# SE-Exp30.net
KiCad netlist of a schematic drawn in EAGLE
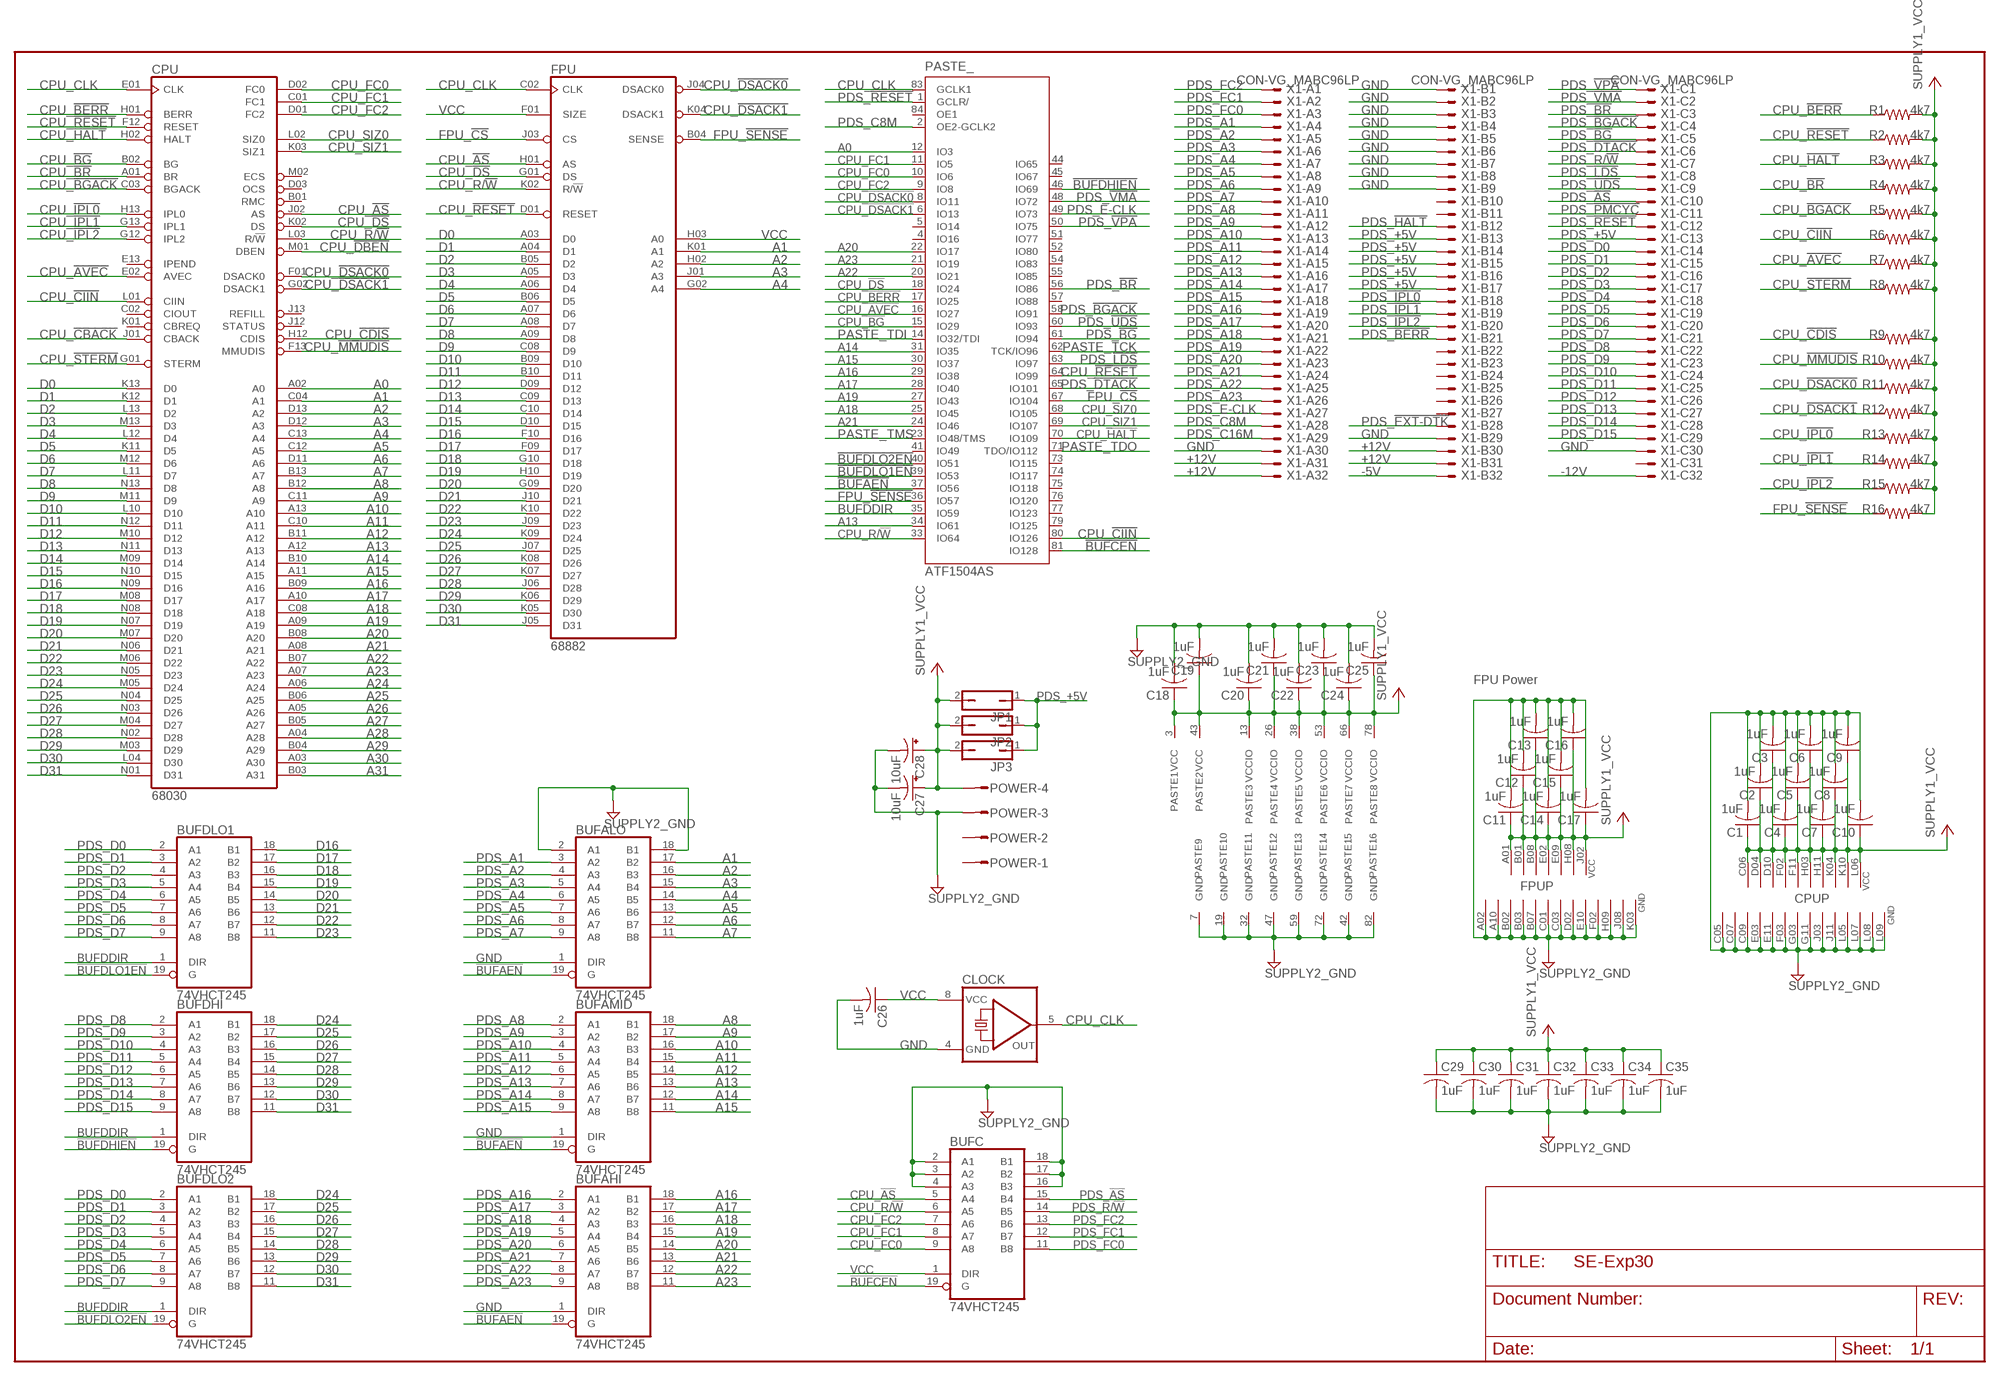
[diagram p0: schematic, sheet 1]

(export (version "E")
  (design (tool "Eeschema 10.0.6"))
  (components
    (comp (ref "BUFAHI")
      (value "74VHCT245")
      (footprint "eagle-import:74XX-US_SO20W")
      (libsource (lib "eagle-import") (part "74XX-US_74245DWLS"))
    )
    (comp (ref "BUFALO")
      (value "74VHCT245")
      (footprint "eagle-import:74XX-US_SO20W")
      (libsource (lib "eagle-import") (part "74XX-US_74245DWLS"))
    )
    (comp (ref "BUFAMID")
      (value "74VHCT245")
      (footprint "eagle-import:74XX-US_SO20W")
      (libsource (lib "eagle-import") (part "74XX-US_74245DWLS"))
    )
    (comp (ref "BUFC")
      (value "74VHCT245")
      (footprint "eagle-import:74XX-US_SO20W")
      (libsource (lib "eagle-import") (part "74XX-US_74245DWLS"))
    )
    (comp (ref "BUFDHI")
      (value "74VHCT245")
      (footprint "eagle-import:74XX-US_SO20W")
      (libsource (lib "eagle-import") (part "74XX-US_74245DWLS"))
    )
    (comp (ref "BUFDLO1")
      (value "74VHCT245")
      (footprint "eagle-import:74XX-US_SO20W")
      (libsource (lib "eagle-import") (part "74XX-US_74245DWLS"))
    )
    (comp (ref "BUFDLO2")
      (value "74VHCT245")
      (footprint "eagle-import:74XX-US_SO20W")
      (libsource (lib "eagle-import") (part "74XX-US_74245DWLS"))
    )
    (comp (ref "C1")
      (value "1uF")
      (footprint "eagle-import:RCL_C0805")
      (libsource (lib "eagle-import") (part "RCL_C-USC0805"))
    )
    (comp (ref "C2")
      (value "1uF")
      (footprint "eagle-import:RCL_C0805")
      (libsource (lib "eagle-import") (part "RCL_C-USC0805"))
    )
    (comp (ref "C3")
      (value "1uF")
      (footprint "eagle-import:RCL_C0805")
      (libsource (lib "eagle-import") (part "RCL_C-USC0805"))
    )
    (comp (ref "C4")
      (value "1uF")
      (footprint "eagle-import:RCL_C0805")
      (libsource (lib "eagle-import") (part "RCL_C-USC0805"))
    )
    (comp (ref "C5")
      (value "1uF")
      (footprint "eagle-import:RCL_C0805")
      (libsource (lib "eagle-import") (part "RCL_C-USC0805"))
    )
    (comp (ref "C6")
      (value "1uF")
      (footprint "eagle-import:RCL_C0805")
      (libsource (lib "eagle-import") (part "RCL_C-USC0805"))
    )
    (comp (ref "C7")
      (value "1uF")
      (footprint "eagle-import:RCL_C0805")
      (libsource (lib "eagle-import") (part "RCL_C-USC0805"))
    )
    (comp (ref "C8")
      (value "1uF")
      (footprint "eagle-import:RCL_C0805")
      (libsource (lib "eagle-import") (part "RCL_C-USC0805"))
    )
    (comp (ref "C9")
      (value "1uF")
      (footprint "eagle-import:RCL_C0805")
      (libsource (lib "eagle-import") (part "RCL_C-USC0805"))
    )
    (comp (ref "C10")
      (value "1uF")
      (footprint "eagle-import:RCL_C0805")
      (libsource (lib "eagle-import") (part "RCL_C-USC0805"))
    )
    (comp (ref "C11")
      (value "1uF")
      (footprint "eagle-import:RCL_C0805")
      (libsource (lib "eagle-import") (part "RCL_C-USC0805"))
    )
    (comp (ref "C12")
      (value "1uF")
      (footprint "eagle-import:RCL_C0805")
      (libsource (lib "eagle-import") (part "RCL_C-USC0805"))
    )
    (comp (ref "C13")
      (value "1uF")
      (footprint "eagle-import:RCL_C0805")
      (libsource (lib "eagle-import") (part "RCL_C-USC0805"))
    )
    (comp (ref "C14")
      (value "1uF")
      (footprint "eagle-import:RCL_C0805")
      (libsource (lib "eagle-import") (part "RCL_C-USC0805"))
    )
    (comp (ref "C15")
      (value "1uF")
      (footprint "eagle-import:RCL_C0805")
      (libsource (lib "eagle-import") (part "RCL_C-USC0805"))
    )
    (comp (ref "C16")
      (value "1uF")
      (footprint "eagle-import:RCL_C0805")
      (libsource (lib "eagle-import") (part "RCL_C-USC0805"))
    )
    (comp (ref "C17")
      (value "1uF")
      (footprint "eagle-import:RCL_C0805")
      (libsource (lib "eagle-import") (part "RCL_C-USC0805"))
    )
    (comp (ref "C18")
      (value "1uF")
      (footprint "eagle-import:RCL_C0805")
      (libsource (lib "eagle-import") (part "RCL_C-USC0805"))
    )
    (comp (ref "C19")
      (value "1uF")
      (footprint "eagle-import:RCL_C0805")
      (libsource (lib "eagle-import") (part "RCL_C-USC0805"))
    )
    (comp (ref "C20")
      (value "1uF")
      (footprint "eagle-import:RCL_C0805")
      (libsource (lib "eagle-import") (part "RCL_C-USC0805"))
    )
    (comp (ref "C21")
      (value "1uF")
      (footprint "eagle-import:RCL_C0805")
      (libsource (lib "eagle-import") (part "RCL_C-USC0805"))
    )
    (comp (ref "C22")
      (value "1uF")
      (footprint "eagle-import:RCL_C0805")
      (libsource (lib "eagle-import") (part "RCL_C-USC0805"))
    )
    (comp (ref "C23")
      (value "1uF")
      (footprint "eagle-import:RCL_C0805")
      (libsource (lib "eagle-import") (part "RCL_C-USC0805"))
    )
    (comp (ref "C24")
      (value "1uF")
      (footprint "eagle-import:RCL_C0805")
      (libsource (lib "eagle-import") (part "RCL_C-USC0805"))
    )
    (comp (ref "C25")
      (value "1uF")
      (footprint "eagle-import:RCL_C0805")
      (libsource (lib "eagle-import") (part "RCL_C-USC0805"))
    )
    (comp (ref "C26")
      (value "1uF")
      (footprint "eagle-import:RCL_C0805")
      (libsource (lib "eagle-import") (part "RCL_C-USC0805"))
    )
    (comp (ref "C27")
      (value "10uF")
      (footprint "eagle-import:RCL_E2,5-5")
      (libsource (lib "eagle-import") (part "RCL_CPOL-USE2.5-5"))
    )
    (comp (ref "C28")
      (value "10uF")
      (footprint "eagle-import:RCL_E2,5-5")
      (libsource (lib "eagle-import") (part "RCL_CPOL-USE2.5-5"))
    )
    (comp (ref "C29")
      (value "1uF")
      (footprint "eagle-import:RCL_C0805")
      (libsource (lib "eagle-import") (part "RCL_C-USC0805"))
    )
    (comp (ref "C30")
      (value "1uF")
      (footprint "eagle-import:RCL_C0805")
      (libsource (lib "eagle-import") (part "RCL_C-USC0805"))
    )
    (comp (ref "C31")
      (value "1uF")
      (footprint "eagle-import:RCL_C0805")
      (libsource (lib "eagle-import") (part "RCL_C-USC0805"))
    )
    (comp (ref "C32")
      (value "1uF")
      (footprint "eagle-import:RCL_C0805")
      (libsource (lib "eagle-import") (part "RCL_C-USC0805"))
    )
    (comp (ref "C33")
      (value "1uF")
      (footprint "eagle-import:RCL_C0805")
      (libsource (lib "eagle-import") (part "RCL_C-USC0805"))
    )
    (comp (ref "C34")
      (value "1uF")
      (footprint "eagle-import:RCL_C0805")
      (libsource (lib "eagle-import") (part "RCL_C-USC0805"))
    )
    (comp (ref "C35")
      (value "1uF")
      (footprint "eagle-import:RCL_C0805")
      (libsource (lib "eagle-import") (part "RCL_C-USC0805"))
    )
    (comp (ref "CLOCK")
      (value "CRYSTAL_QG5460")
      (footprint "eagle-import:CRYSTAL_DIL08S")
      (libsource (lib "eagle-import") (part "CRYSTAL_QG5460"))
    )
    (comp (ref "CPU")
      (value "68030")
      (footprint "eagle-import:MICRO-MC68000_MPGA128")
      (fields (field (name "MF") "MOTOROLA") (field (name "MPN") "MC68030RC50C"))
      (libsource (lib "eagle-import") (part "MICRO-MC68000_MC68030RC"))
    )
    (comp (ref "FPU")
      (value "68882")
      (footprint "eagle-import:MICRO-MC68000_MPGA68")
      (libsource (lib "eagle-import") (part "MICRO-MC68000_MC68881RC"))
    )
    (comp (ref "JP1")
      (value "JUMPER_JP1Q")
      (footprint "eagle-import:JUMPER_JP1")
      (libsource (lib "eagle-import") (part "JUMPER_JP1Q"))
    )
    (comp (ref "JP2")
      (value "JUMPER_JP1Q")
      (footprint "eagle-import:JUMPER_JP1")
      (libsource (lib "eagle-import") (part "JUMPER_JP1Q"))
    )
    (comp (ref "JP3")
      (value "JUMPER_JP1Q")
      (footprint "eagle-import:JUMPER_JP1")
      (libsource (lib "eagle-import") (part "JUMPER_JP1Q"))
    )
    (comp (ref "PASTE")
      (value "ATF1504AS")
      (footprint "eagle-import:SE-EXP30_S84")
      (libsource (lib "eagle-import") (part "SE-EXP30_EPM7128-J84S"))
    )
    (comp (ref "POWER")
      (value "CON-AMP-MT_L04P")
      (footprint "eagle-import:CON-AMP-MT_L04P")
      (libsource (lib "eagle-import") (part "CON-AMP-MT_L04P"))
    )
    (comp (ref "R1")
      (value "4k7")
      (footprint "eagle-import:RCL_R0805")
      (libsource (lib "eagle-import") (part "RCL_R-US_R0805"))
    )
    (comp (ref "R2")
      (value "4k7")
      (footprint "eagle-import:RCL_R0805")
      (libsource (lib "eagle-import") (part "RCL_R-US_R0805"))
    )
    (comp (ref "R3")
      (value "4k7")
      (footprint "eagle-import:RCL_R0805")
      (libsource (lib "eagle-import") (part "RCL_R-US_R0805"))
    )
    (comp (ref "R4")
      (value "4k7")
      (footprint "eagle-import:RCL_R0805")
      (libsource (lib "eagle-import") (part "RCL_R-US_R0805"))
    )
    (comp (ref "R5")
      (value "4k7")
      (footprint "eagle-import:RCL_R0805")
      (libsource (lib "eagle-import") (part "RCL_R-US_R0805"))
    )
    (comp (ref "R6")
      (value "4k7")
      (footprint "eagle-import:RCL_R0805")
      (libsource (lib "eagle-import") (part "RCL_R-US_R0805"))
    )
    (comp (ref "R7")
      (value "4k7")
      (footprint "eagle-import:RCL_R0805")
      (libsource (lib "eagle-import") (part "RCL_R-US_R0805"))
    )
    (comp (ref "R8")
      (value "4k7")
      (footprint "eagle-import:RCL_R0805")
      (libsource (lib "eagle-import") (part "RCL_R-US_R0805"))
    )
    (comp (ref "R9")
      (value "4k7")
      (footprint "eagle-import:RCL_R0805")
      (libsource (lib "eagle-import") (part "RCL_R-US_R0805"))
    )
    (comp (ref "R10")
      (value "4k7")
      (footprint "eagle-import:RCL_R0805")
      (libsource (lib "eagle-import") (part "RCL_R-US_R0805"))
    )
    (comp (ref "R11")
      (value "4k7")
      (footprint "eagle-import:RCL_R0805")
      (libsource (lib "eagle-import") (part "RCL_R-US_R0805"))
    )
    (comp (ref "R12")
      (value "4k7")
      (footprint "eagle-import:RCL_R0805")
      (libsource (lib "eagle-import") (part "RCL_R-US_R0805"))
    )
    (comp (ref "R13")
      (value "4k7")
      (footprint "eagle-import:RCL_R0805")
      (libsource (lib "eagle-import") (part "RCL_R-US_R0805"))
    )
    (comp (ref "R14")
      (value "4k7")
      (footprint "eagle-import:RCL_R0805")
      (libsource (lib "eagle-import") (part "RCL_R-US_R0805"))
    )
    (comp (ref "R15")
      (value "4k7")
      (footprint "eagle-import:RCL_R0805")
      (libsource (lib "eagle-import") (part "RCL_R-US_R0805"))
    )
    (comp (ref "R16")
      (value "4k7")
      (footprint "eagle-import:RCL_R0805")
      (libsource (lib "eagle-import") (part "RCL_R-US_R0805"))
    )
    (comp (ref "X1")
      (value "CON-VG_MABC96LP")
      (footprint "eagle-import:CON-VG_MABC96LP")
      (libsource (lib "eagle-import") (part "CON-VG_MABC96LP"))
    )
  )
  (nets
    (net (code "1") (name "/+12V") (class "Default")
      (node (ref "X1") (pin "A31") (pinfunction "S_A31") (pintype "passive"))
      (node (ref "X1") (pin "A32") (pinfunction "S_A32") (pintype "passive"))
      (node (ref "X1") (pin "B30") (pinfunction "S_B30") (pintype "passive"))
      (node (ref "X1") (pin "B31") (pinfunction "S_B31") (pintype "passive"))
    )
    (net (code "2") (name "/-5V") (class "Default")
      (node (ref "X1") (pin "B32") (pinfunction "S_B32") (pintype "passive"))
    )
    (net (code "3") (name "/-12V") (class "Default")
      (node (ref "X1") (pin "C32") (pinfunction "S_C32") (pintype "passive"))
    )
    (net (code "4") (name "/A0") (class "Default")
      (node (ref "CPU") (pin "A02") (pinfunction "A0_A02") (pintype "output"))
      (node (ref "PASTE") (pin "12") (pinfunction "IO3_12") (pintype "bidirectional"))
    )
    (net (code "5") (name "/A1") (class "Default")
      (node (ref "BUFALO") (pin "17") (pinfunction "B2_17") (pintype "bidirectional"))
      (node (ref "CPU") (pin "C04") (pinfunction "A1_C04") (pintype "output"))
      (node (ref "FPU") (pin "K01") (pinfunction "A1_K01") (pintype "input"))
    )
    (net (code "6") (name "/A2") (class "Default")
      (node (ref "BUFALO") (pin "16") (pinfunction "B3_16") (pintype "bidirectional"))
      (node (ref "CPU") (pin "D13") (pinfunction "A2_D13") (pintype "output"))
      (node (ref "FPU") (pin "H02") (pinfunction "A2_H02") (pintype "input"))
    )
    (net (code "7") (name "/A3") (class "Default")
      (node (ref "BUFALO") (pin "15") (pinfunction "B4_15") (pintype "bidirectional"))
      (node (ref "CPU") (pin "D12") (pinfunction "A3_D12") (pintype "output"))
      (node (ref "FPU") (pin "J01") (pinfunction "A3_J01") (pintype "input"))
    )
    (net (code "8") (name "/A4") (class "Default")
      (node (ref "BUFALO") (pin "14") (pinfunction "B5_14") (pintype "bidirectional"))
      (node (ref "CPU") (pin "C13") (pinfunction "A4_C13") (pintype "output"))
      (node (ref "FPU") (pin "G02") (pinfunction "A4_G02") (pintype "input"))
    )
    (net (code "9") (name "/A5") (class "Default")
      (node (ref "BUFALO") (pin "13") (pinfunction "B6_13") (pintype "bidirectional"))
      (node (ref "CPU") (pin "C12") (pinfunction "A5_C12") (pintype "output"))
    )
    (net (code "10") (name "/A6") (class "Default")
      (node (ref "BUFALO") (pin "12") (pinfunction "B7_12") (pintype "bidirectional"))
      (node (ref "CPU") (pin "D11") (pinfunction "A6_D11") (pintype "output"))
    )
    (net (code "11") (name "/A7") (class "Default")
      (node (ref "BUFALO") (pin "11") (pinfunction "B8_11") (pintype "bidirectional"))
      (node (ref "CPU") (pin "B13") (pinfunction "A7_B13") (pintype "output"))
    )
    (net (code "12") (name "/A8") (class "Default")
      (node (ref "BUFAMID") (pin "18") (pinfunction "B1_18") (pintype "bidirectional"))
      (node (ref "CPU") (pin "B12") (pinfunction "A8_B12") (pintype "output"))
    )
    (net (code "13") (name "/A9") (class "Default")
      (node (ref "BUFAMID") (pin "17") (pinfunction "B2_17") (pintype "bidirectional"))
      (node (ref "CPU") (pin "C11") (pinfunction "A9_C11") (pintype "output"))
    )
    (net (code "14") (name "/A10") (class "Default")
      (node (ref "BUFAMID") (pin "16") (pinfunction "B3_16") (pintype "bidirectional"))
      (node (ref "CPU") (pin "A13") (pinfunction "A10_A13") (pintype "output"))
    )
    (net (code "15") (name "/A11") (class "Default")
      (node (ref "BUFAMID") (pin "15") (pinfunction "B4_15") (pintype "bidirectional"))
      (node (ref "CPU") (pin "C10") (pinfunction "A11_C10") (pintype "output"))
    )
    (net (code "16") (name "/A12") (class "Default")
      (node (ref "BUFAMID") (pin "14") (pinfunction "B5_14") (pintype "bidirectional"))
      (node (ref "CPU") (pin "B11") (pinfunction "A12_B11") (pintype "output"))
    )
    (net (code "17") (name "/A13") (class "Default")
      (node (ref "BUFAMID") (pin "13") (pinfunction "B6_13") (pintype "bidirectional"))
      (node (ref "CPU") (pin "A12") (pinfunction "A13_A12") (pintype "output"))
      (node (ref "PASTE") (pin "34") (pinfunction "IO61_34") (pintype "bidirectional"))
    )
    (net (code "18") (name "/A14") (class "Default")
      (node (ref "BUFAMID") (pin "12") (pinfunction "B7_12") (pintype "bidirectional"))
      (node (ref "CPU") (pin "B10") (pinfunction "A14_B10") (pintype "output"))
      (node (ref "PASTE") (pin "31") (pinfunction "IO35_31") (pintype "bidirectional"))
    )
    (net (code "19") (name "/A15") (class "Default")
      (node (ref "BUFAMID") (pin "11") (pinfunction "B8_11") (pintype "bidirectional"))
      (node (ref "CPU") (pin "A11") (pinfunction "A15_A11") (pintype "output"))
      (node (ref "PASTE") (pin "30") (pinfunction "IO37_30") (pintype "bidirectional"))
    )
    (net (code "20") (name "/A16") (class "Default")
      (node (ref "BUFAHI") (pin "18") (pinfunction "B1_18") (pintype "bidirectional"))
      (node (ref "CPU") (pin "B09") (pinfunction "A16_B09") (pintype "output"))
      (node (ref "PASTE") (pin "29") (pinfunction "IO38_29") (pintype "bidirectional"))
    )
    (net (code "21") (name "/A17") (class "Default")
      (node (ref "BUFAHI") (pin "17") (pinfunction "B2_17") (pintype "bidirectional"))
      (node (ref "CPU") (pin "A10") (pinfunction "A17_A10") (pintype "output"))
      (node (ref "PASTE") (pin "28") (pinfunction "IO40_28") (pintype "bidirectional"))
    )
    (net (code "22") (name "/A18") (class "Default")
      (node (ref "BUFAHI") (pin "16") (pinfunction "B3_16") (pintype "bidirectional"))
      (node (ref "CPU") (pin "C08") (pinfunction "A18_C08") (pintype "output"))
      (node (ref "PASTE") (pin "25") (pinfunction "IO45_25") (pintype "bidirectional"))
    )
    (net (code "23") (name "/A19") (class "Default")
      (node (ref "BUFAHI") (pin "15") (pinfunction "B4_15") (pintype "bidirectional"))
      (node (ref "CPU") (pin "A09") (pinfunction "A19_A09") (pintype "output"))
      (node (ref "PASTE") (pin "27") (pinfunction "IO43_27") (pintype "bidirectional"))
    )
    (net (code "24") (name "/A20") (class "Default")
      (node (ref "BUFAHI") (pin "14") (pinfunction "B5_14") (pintype "bidirectional"))
      (node (ref "CPU") (pin "B08") (pinfunction "A20_B08") (pintype "output"))
      (node (ref "PASTE") (pin "22") (pinfunction "IO17_22") (pintype "bidirectional"))
    )
    (net (code "25") (name "/A21") (class "Default")
      (node (ref "BUFAHI") (pin "13") (pinfunction "B6_13") (pintype "bidirectional"))
      (node (ref "CPU") (pin "A08") (pinfunction "A21_A08") (pintype "output"))
      (node (ref "PASTE") (pin "24") (pinfunction "IO46_24") (pintype "bidirectional"))
    )
    (net (code "26") (name "/A22") (class "Default")
      (node (ref "BUFAHI") (pin "12") (pinfunction "B7_12") (pintype "bidirectional"))
      (node (ref "CPU") (pin "B07") (pinfunction "A22_B07") (pintype "output"))
      (node (ref "PASTE") (pin "20") (pinfunction "IO21_20") (pintype "bidirectional"))
    )
    (net (code "27") (name "/A23") (class "Default")
      (node (ref "BUFAHI") (pin "11") (pinfunction "B8_11") (pintype "bidirectional"))
      (node (ref "CPU") (pin "A07") (pinfunction "A23_A07") (pintype "output"))
      (node (ref "PASTE") (pin "21") (pinfunction "IO19_21") (pintype "bidirectional"))
    )
    (net (code "28") (name "/A24") (class "Default")
      (node (ref "CPU") (pin "A06") (pinfunction "A24_A06") (pintype "output"))
    )
    (net (code "29") (name "/A25") (class "Default")
      (node (ref "CPU") (pin "B06") (pinfunction "A25_B06") (pintype "output"))
    )
    (net (code "30") (name "/A26") (class "Default")
      (node (ref "CPU") (pin "A05") (pinfunction "A26_A05") (pintype "output"))
    )
    (net (code "31") (name "/A27") (class "Default")
      (node (ref "CPU") (pin "B05") (pinfunction "A27_B05") (pintype "output"))
    )
    (net (code "32") (name "/A28") (class "Default")
      (node (ref "CPU") (pin "A04") (pinfunction "A28_A04") (pintype "output"))
    )
    (net (code "33") (name "/A29") (class "Default")
      (node (ref "CPU") (pin "B04") (pinfunction "A29_B04") (pintype "output"))
    )
    (net (code "34") (name "/A30") (class "Default")
      (node (ref "CPU") (pin "A03") (pinfunction "A30_A03") (pintype "output"))
    )
    (net (code "35") (name "/A31") (class "Default")
      (node (ref "CPU") (pin "B03") (pinfunction "A31_B03") (pintype "output"))
    )
    (net (code "36") (name "/BUFDDIR") (class "Default")
      (node (ref "BUFDHI") (pin "1") (pinfunction "DIR_1") (pintype "input"))
      (node (ref "BUFDLO1") (pin "1") (pinfunction "DIR_1") (pintype "input"))
      (node (ref "BUFDLO2") (pin "1") (pinfunction "DIR_1") (pintype "input"))
      (node (ref "PASTE") (pin "35") (pinfunction "IO59_35") (pintype "bidirectional"))
    )
    (net (code "37") (name "/CPU_CLK") (class "Default")
      (node (ref "CLOCK") (pin "5") (pinfunction "OUT_5") (pintype "output"))
      (node (ref "CPU") (pin "E01") (pinfunction "CLK_E01") (pintype "input"))
      (node (ref "FPU") (pin "C02") (pinfunction "CLK_C02") (pintype "input"))
      (node (ref "PASTE") (pin "83") (pinfunction "GCLK1_83") (pintype "input"))
    )
    (net (code "38") (name "/CPU_FC0") (class "Default")
      (node (ref "BUFC") (pin "9") (pinfunction "A8_9") (pintype "bidirectional"))
      (node (ref "CPU") (pin "D02") (pinfunction "FC0_D02") (pintype "output"))
      (node (ref "PASTE") (pin "10") (pinfunction "IO6_10") (pintype "bidirectional"))
    )
    (net (code "39") (name "/CPU_FC1") (class "Default")
      (node (ref "BUFC") (pin "8") (pinfunction "A7_8") (pintype "bidirectional"))
      (node (ref "CPU") (pin "C01") (pinfunction "FC1_C01") (pintype "output"))
      (node (ref "PASTE") (pin "11") (pinfunction "IO5_11") (pintype "bidirectional"))
    )
    (net (code "40") (name "/CPU_FC2") (class "Default")
      (node (ref "BUFC") (pin "7") (pinfunction "A6_7") (pintype "bidirectional"))
      (node (ref "CPU") (pin "D01") (pinfunction "FC2_D01") (pintype "output"))
      (node (ref "PASTE") (pin "9") (pinfunction "IO8_9") (pintype "bidirectional"))
    )
    (net (code "41") (name "/CPU_R{slash}~{W}") (class "Default")
      (node (ref "BUFC") (pin "6") (pinfunction "A5_6") (pintype "bidirectional"))
      (node (ref "CPU") (pin "L03") (pinfunction "R/~{W}_L03") (pintype "output"))
      (node (ref "FPU") (pin "K02") (pinfunction "R/~{W}_K02") (pintype "input"))
      (node (ref "PASTE") (pin "33") (pinfunction "IO64_33") (pintype "bidirectional"))
    )
    (net (code "42") (name "/CPU_SIZ0") (class "Default")
      (node (ref "CPU") (pin "L02") (pinfunction "SIZ0_L02") (pintype "output"))
      (node (ref "PASTE") (pin "68") (pinfunction "IO105_68") (pintype "bidirectional"))
    )
    (net (code "43") (name "/CPU_SIZ1") (class "Default")
      (node (ref "CPU") (pin "K03") (pinfunction "SIZ1_K03") (pintype "output"))
      (node (ref "PASTE") (pin "69") (pinfunction "IO107_69") (pintype "bidirectional"))
    )
    (net (code "44") (name "/CPU_~{AS}") (class "Default")
      (node (ref "BUFC") (pin "5") (pinfunction "A4_5") (pintype "bidirectional"))
      (node (ref "CPU") (pin "J02") (pinfunction "AS_J02") (pintype "output"))
      (node (ref "FPU") (pin "H01") (pinfunction "AS_H01") (pintype "input"))
    )
    (net (code "45") (name "/CPU_~{AVEC}") (class "Default")
      (node (ref "CPU") (pin "E02") (pinfunction "AVEC_E02") (pintype "input"))
      (node (ref "PASTE") (pin "16") (pinfunction "IO27_16") (pintype "bidirectional"))
      (node (ref "R7") (pin "1") (pinfunction "1_1") (pintype "passive"))
    )
    (net (code "46") (name "/CPU_~{BERR}") (class "Default")
      (node (ref "CPU") (pin "H01") (pinfunction "BERR_H01") (pintype "input"))
      (node (ref "PASTE") (pin "17") (pinfunction "IO25_17") (pintype "bidirectional"))
      (node (ref "R1") (pin "1") (pinfunction "1_1") (pintype "passive"))
    )
    (net (code "47") (name "/CPU_~{BGACK}") (class "Default")
      (node (ref "CPU") (pin "C03") (pinfunction "BGACK_C03") (pintype "input"))
      (node (ref "R5") (pin "1") (pinfunction "1_1") (pintype "passive"))
    )
    (net (code "48") (name "/CPU_~{BG}") (class "Default")
      (node (ref "CPU") (pin "B02") (pinfunction "BG_B02") (pintype "output"))
      (node (ref "PASTE") (pin "15") (pinfunction "IO29_15") (pintype "bidirectional"))
    )
    (net (code "49") (name "/CPU_~{BR}") (class "Default")
      (node (ref "CPU") (pin "A01") (pinfunction "BR_A01") (pintype "input"))
      (node (ref "R4") (pin "1") (pinfunction "1_1") (pintype "passive"))
    )
    (net (code "50") (name "/CPU_~{CBACK}") (class "Default")
      (node (ref "CPU") (pin "J01") (pinfunction "CBACK_J01") (pintype "input"))
    )
    (net (code "51") (name "/CPU_~{CDIS}") (class "Default")
      (node (ref "CPU") (pin "H12") (pinfunction "CDIS_H12") (pintype "input"))
      (node (ref "R9") (pin "1") (pinfunction "1_1") (pintype "passive"))
    )
    (net (code "52") (name "/CPU_~{CIIN}") (class "Default")
      (node (ref "CPU") (pin "L01") (pinfunction "CIIN_L01") (pintype "input"))
      (node (ref "PASTE") (pin "80") (pinfunction "IO126_80") (pintype "bidirectional"))
      (node (ref "R6") (pin "1") (pinfunction "1_1") (pintype "passive"))
    )
    (net (code "53") (name "/CPU_~{DBEN}") (class "Default")
      (node (ref "CPU") (pin "M01") (pinfunction "DBEN_M01") (pintype "output"))
    )
    (net (code "54") (name "/CPU_~{DSACK0}") (class "Default")
      (node (ref "CPU") (pin "F01") (pinfunction "DSACK0_F01") (pintype "input"))
      (node (ref "FPU") (pin "J04") (pinfunction "DSACK0_J04") (pintype "output"))
      (node (ref "PASTE") (pin "8") (pinfunction "IO11_8") (pintype "bidirectional"))
      (node (ref "R11") (pin "1") (pinfunction "1_1") (pintype "passive"))
    )
    (net (code "55") (name "/CPU_~{DSACK1}") (class "Default")
      (node (ref "CPU") (pin "G02") (pinfunction "DSACK1_G02") (pintype "input"))
      (node (ref "FPU") (pin "K04") (pinfunction "DSACK1_K04") (pintype "output"))
      (node (ref "PASTE") (pin "6") (pinfunction "IO13_6") (pintype "bidirectional"))
      (node (ref "R12") (pin "1") (pinfunction "1_1") (pintype "passive"))
    )
    (net (code "56") (name "/CPU_~{DS}") (class "Default")
      (node (ref "CPU") (pin "K02") (pinfunction "DS_K02") (pintype "output"))
      (node (ref "FPU") (pin "G01") (pinfunction "DS_G01") (pintype "input"))
      (node (ref "PASTE") (pin "18") (pinfunction "IO24_18") (pintype "bidirectional"))
    )
    (net (code "57") (name "/CPU_~{HALT}") (class "Default")
      (node (ref "CPU") (pin "H02") (pinfunction "HALT_H02") (pintype "input"))
      (node (ref "PASTE") (pin "70") (pinfunction "IO109_70") (pintype "bidirectional"))
      (node (ref "R3") (pin "1") (pinfunction "1_1") (pintype "passive"))
    )
    (net (code "58") (name "/CPU_~{IPL0}") (class "Default")
      (node (ref "CPU") (pin "H13") (pinfunction "IPL0_H13") (pintype "input"))
      (node (ref "R13") (pin "1") (pinfunction "1_1") (pintype "passive"))
    )
    (net (code "59") (name "/CPU_~{IPL1}") (class "Default")
      (node (ref "CPU") (pin "G13") (pinfunction "IPL1_G13") (pintype "input"))
      (node (ref "R14") (pin "1") (pinfunction "1_1") (pintype "passive"))
    )
    (net (code "60") (name "/CPU_~{IPL2}") (class "Default")
      (node (ref "CPU") (pin "G12") (pinfunction "IPL2_G12") (pintype "input"))
      (node (ref "R15") (pin "1") (pinfunction "1_1") (pintype "passive"))
    )
    (net (code "61") (name "/CPU_~{MMUDIS}") (class "Default")
      (node (ref "CPU") (pin "F13") (pinfunction "MMUDIS_F13") (pintype "input"))
      (node (ref "R10") (pin "1") (pinfunction "1_1") (pintype "passive"))
    )
    (net (code "62") (name "/CPU_~{RESET}") (class "Default")
      (node (ref "CPU") (pin "F12") (pinfunction "RESET_F12") (pintype "bidirectional"))
      (node (ref "FPU") (pin "D01") (pinfunction "RESET_D01") (pintype "input"))
      (node (ref "PASTE") (pin "64") (pinfunction "IO99_64") (pintype "bidirectional"))
      (node (ref "R2") (pin "1") (pinfunction "1_1") (pintype "passive"))
    )
    (net (code "63") (name "/CPU_~{STERM}") (class "Default")
      (node (ref "CPU") (pin "G01") (pinfunction "STERM_G01") (pintype "input"))
      (node (ref "R8") (pin "1") (pinfunction "1_1") (pintype "passive"))
    )
    (net (code "64") (name "/D0") (class "Default")
      (node (ref "CPU") (pin "K13") (pinfunction "D0_K13") (pintype "bidirectional"))
      (node (ref "FPU") (pin "A03") (pinfunction "D0_A03") (pintype "bidirectional"))
    )
    (net (code "65") (name "/D1") (class "Default")
      (node (ref "CPU") (pin "K12") (pinfunction "D1_K12") (pintype "bidirectional"))
      (node (ref "FPU") (pin "A04") (pinfunction "D1_A04") (pintype "bidirectional"))
    )
    (net (code "66") (name "/D2") (class "Default")
      (node (ref "CPU") (pin "L13") (pinfunction "D2_L13") (pintype "bidirectional"))
      (node (ref "FPU") (pin "B05") (pinfunction "D2_B05") (pintype "bidirectional"))
    )
    (net (code "67") (name "/D3") (class "Default")
      (node (ref "CPU") (pin "M13") (pinfunction "D3_M13") (pintype "bidirectional"))
      (node (ref "FPU") (pin "A05") (pinfunction "D3_A05") (pintype "bidirectional"))
    )
    (net (code "68") (name "/D4") (class "Default")
      (node (ref "CPU") (pin "L12") (pinfunction "D4_L12") (pintype "bidirectional"))
      (node (ref "FPU") (pin "A06") (pinfunction "D4_A06") (pintype "bidirectional"))
    )
    (net (code "69") (name "/D5") (class "Default")
      (node (ref "CPU") (pin "K11") (pinfunction "D5_K11") (pintype "bidirectional"))
      (node (ref "FPU") (pin "B06") (pinfunction "D5_B06") (pintype "bidirectional"))
    )
    (net (code "70") (name "/D6") (class "Default")
      (node (ref "CPU") (pin "M12") (pinfunction "D6_M12") (pintype "bidirectional"))
      (node (ref "FPU") (pin "A07") (pinfunction "D6_A07") (pintype "bidirectional"))
    )
    (net (code "71") (name "/D7") (class "Default")
      (node (ref "CPU") (pin "L11") (pinfunction "D7_L11") (pintype "bidirectional"))
      (node (ref "FPU") (pin "A08") (pinfunction "D7_A08") (pintype "bidirectional"))
    )
    (net (code "72") (name "/D8") (class "Default")
      (node (ref "CPU") (pin "N13") (pinfunction "D8_N13") (pintype "bidirectional"))
      (node (ref "FPU") (pin "A09") (pinfunction "D8_A09") (pintype "bidirectional"))
    )
    (net (code "73") (name "/D9") (class "Default")
      (node (ref "CPU") (pin "M11") (pinfunction "D9_M11") (pintype "bidirectional"))
      (node (ref "FPU") (pin "C08") (pinfunction "D9_C08") (pintype "bidirectional"))
    )
    (net (code "74") (name "/D10") (class "Default")
      (node (ref "CPU") (pin "L10") (pinfunction "D10_L10") (pintype "bidirectional"))
      (node (ref "FPU") (pin "B09") (pinfunction "D10_B09") (pintype "bidirectional"))
    )
    (net (code "75") (name "/D11") (class "Default")
      (node (ref "CPU") (pin "N12") (pinfunction "D11_N12") (pintype "bidirectional"))
      (node (ref "FPU") (pin "B10") (pinfunction "D11_B10") (pintype "bidirectional"))
    )
    (net (code "76") (name "/D12") (class "Default")
      (node (ref "CPU") (pin "M10") (pinfunction "D12_M10") (pintype "bidirectional"))
      (node (ref "FPU") (pin "D09") (pinfunction "D12_D09") (pintype "bidirectional"))
    )
    (net (code "77") (name "/D13") (class "Default")
      (node (ref "CPU") (pin "N11") (pinfunction "D13_N11") (pintype "bidirectional"))
      (node (ref "FPU") (pin "C09") (pinfunction "D13_C09") (pintype "bidirectional"))
    )
    (net (code "78") (name "/D14") (class "Default")
      (node (ref "CPU") (pin "M09") (pinfunction "D14_M09") (pintype "bidirectional"))
      (node (ref "FPU") (pin "C10") (pinfunction "D14_C10") (pintype "bidirectional"))
    )
    (net (code "79") (name "/D15") (class "Default")
      (node (ref "CPU") (pin "N10") (pinfunction "D15_N10") (pintype "bidirectional"))
      (node (ref "FPU") (pin "D10") (pinfunction "D15_D10") (pintype "bidirectional"))
    )
    (net (code "80") (name "/D16") (class "Default")
      (node (ref "BUFDLO1") (pin "18") (pinfunction "B1_18") (pintype "bidirectional"))
      (node (ref "CPU") (pin "N09") (pinfunction "D16_N09") (pintype "bidirectional"))
      (node (ref "FPU") (pin "F10") (pinfunction "D16_F10") (pintype "bidirectional"))
    )
    (net (code "81") (name "/D17") (class "Default")
      (node (ref "BUFDLO1") (pin "17") (pinfunction "B2_17") (pintype "bidirectional"))
      (node (ref "CPU") (pin "M08") (pinfunction "D17_M08") (pintype "bidirectional"))
      (node (ref "FPU") (pin "F09") (pinfunction "D17_F09") (pintype "bidirectional"))
    )
    (net (code "82") (name "/D18") (class "Default")
      (node (ref "BUFDLO1") (pin "16") (pinfunction "B3_16") (pintype "bidirectional"))
      (node (ref "CPU") (pin "N08") (pinfunction "D18_N08") (pintype "bidirectional"))
      (node (ref "FPU") (pin "G10") (pinfunction "D18_G10") (pintype "bidirectional"))
    )
    (net (code "83") (name "/D19") (class "Default")
      (node (ref "BUFDLO1") (pin "15") (pinfunction "B4_15") (pintype "bidirectional"))
      (node (ref "CPU") (pin "N07") (pinfunction "D19_N07") (pintype "bidirectional"))
      (node (ref "FPU") (pin "H10") (pinfunction "D19_H10") (pintype "bidirectional"))
    )
    (net (code "84") (name "/D20") (class "Default")
      (node (ref "BUFDLO1") (pin "14") (pinfunction "B5_14") (pintype "bidirectional"))
      (node (ref "CPU") (pin "M07") (pinfunction "D20_M07") (pintype "bidirectional"))
      (node (ref "FPU") (pin "G09") (pinfunction "D20_G09") (pintype "bidirectional"))
    )
    (net (code "85") (name "/D21") (class "Default")
      (node (ref "BUFDLO1") (pin "13") (pinfunction "B6_13") (pintype "bidirectional"))
      (node (ref "CPU") (pin "N06") (pinfunction "D21_N06") (pintype "bidirectional"))
      (node (ref "FPU") (pin "J10") (pinfunction "D21_J10") (pintype "bidirectional"))
    )
    (net (code "86") (name "/D22") (class "Default")
      (node (ref "BUFDLO1") (pin "12") (pinfunction "B7_12") (pintype "bidirectional"))
      (node (ref "CPU") (pin "M06") (pinfunction "D22_M06") (pintype "bidirectional"))
      (node (ref "FPU") (pin "K10") (pinfunction "D22_K10") (pintype "bidirectional"))
    )
    (net (code "87") (name "/D23") (class "Default")
      (node (ref "BUFDLO1") (pin "11") (pinfunction "B8_11") (pintype "bidirectional"))
      (node (ref "CPU") (pin "N05") (pinfunction "D23_N05") (pintype "bidirectional"))
      (node (ref "FPU") (pin "J09") (pinfunction "D23_J09") (pintype "bidirectional"))
    )
    (net (code "88") (name "/D24") (class "Default")
      (node (ref "BUFDHI") (pin "18") (pinfunction "B1_18") (pintype "bidirectional"))
      (node (ref "BUFDLO2") (pin "18") (pinfunction "B1_18") (pintype "bidirectional"))
      (node (ref "CPU") (pin "M05") (pinfunction "D24_M05") (pintype "bidirectional"))
      (node (ref "FPU") (pin "K09") (pinfunction "D24_K09") (pintype "bidirectional"))
    )
    (net (code "89") (name "/D25") (class "Default")
      (node (ref "BUFDHI") (pin "17") (pinfunction "B2_17") (pintype "bidirectional"))
      (node (ref "BUFDLO2") (pin "17") (pinfunction "B2_17") (pintype "bidirectional"))
      (node (ref "CPU") (pin "N04") (pinfunction "D25_N04") (pintype "bidirectional"))
      (node (ref "FPU") (pin "J07") (pinfunction "D25_J07") (pintype "bidirectional"))
    )
    (net (code "90") (name "/D26") (class "Default")
      (node (ref "BUFDHI") (pin "16") (pinfunction "B3_16") (pintype "bidirectional"))
      (node (ref "BUFDLO2") (pin "16") (pinfunction "B3_16") (pintype "bidirectional"))
      (node (ref "CPU") (pin "N03") (pinfunction "D26_N03") (pintype "bidirectional"))
      (node (ref "FPU") (pin "K08") (pinfunction "D26_K08") (pintype "bidirectional"))
    )
    (net (code "91") (name "/D27") (class "Default")
      (node (ref "BUFDHI") (pin "15") (pinfunction "B4_15") (pintype "bidirectional"))
      (node (ref "BUFDLO2") (pin "15") (pinfunction "B4_15") (pintype "bidirectional"))
      (node (ref "CPU") (pin "M04") (pinfunction "D27_M04") (pintype "bidirectional"))
      (node (ref "FPU") (pin "K07") (pinfunction "D27_K07") (pintype "bidirectional"))
    )
    (net (code "92") (name "/D28") (class "Default")
      (node (ref "BUFDHI") (pin "14") (pinfunction "B5_14") (pintype "bidirectional"))
      (node (ref "BUFDLO2") (pin "14") (pinfunction "B5_14") (pintype "bidirectional"))
      (node (ref "CPU") (pin "N02") (pinfunction "D28_N02") (pintype "bidirectional"))
      (node (ref "FPU") (pin "J06") (pinfunction "D28_J06") (pintype "bidirectional"))
    )
    (net (code "93") (name "/D29") (class "Default")
      (node (ref "BUFDHI") (pin "13") (pinfunction "B6_13") (pintype "bidirectional"))
      (node (ref "BUFDLO2") (pin "13") (pinfunction "B6_13") (pintype "bidirectional"))
      (node (ref "CPU") (pin "M03") (pinfunction "D29_M03") (pintype "bidirectional"))
      (node (ref "FPU") (pin "K06") (pinfunction "D29_K06") (pintype "bidirectional"))
    )
    (net (code "94") (name "/D30") (class "Default")
      (node (ref "BUFDHI") (pin "12") (pinfunction "B7_12") (pintype "bidirectional"))
      (node (ref "BUFDLO2") (pin "12") (pinfunction "B7_12") (pintype "bidirectional"))
      (node (ref "CPU") (pin "L04") (pinfunction "D30_L04") (pintype "bidirectional"))
      (node (ref "FPU") (pin "K05") (pinfunction "D30_K05") (pintype "bidirectional"))
    )
    (net (code "95") (name "/D31") (class "Default")
      (node (ref "BUFDHI") (pin "11") (pinfunction "B8_11") (pintype "bidirectional"))
      (node (ref "BUFDLO2") (pin "11") (pinfunction "B8_11") (pintype "bidirectional"))
      (node (ref "CPU") (pin "N01") (pinfunction "D31_N01") (pintype "bidirectional"))
      (node (ref "FPU") (pin "J05") (pinfunction "D31_J05") (pintype "bidirectional"))
    )
    (net (code "96") (name "/FPU_~{CS}") (class "Default")
      (node (ref "FPU") (pin "J03") (pinfunction "CS_J03") (pintype "input"))
      (node (ref "PASTE") (pin "67") (pinfunction "IO104_67") (pintype "bidirectional"))
    )
    (net (code "97") (name "/FPU_~{SENSE}") (class "Default")
      (node (ref "FPU") (pin "B04") (pinfunction "SENSE_B04") (pintype "bidirectional"))
      (node (ref "PASTE") (pin "36") (pinfunction "IO57_36") (pintype "bidirectional"))
      (node (ref "R16") (pin "1") (pinfunction "1_1") (pintype "passive"))
    )
    (net (code "98") (name "/PASTE_TCK") (class "Default")
      (node (ref "PASTE") (pin "62") (pinfunction "TCK/IO96_62") (pintype "bidirectional"))
    )
    (net (code "99") (name "/PASTE_TDI") (class "Default")
      (node (ref "PASTE") (pin "14") (pinfunction "IO32/TDI_14") (pintype "bidirectional"))
    )
    (net (code "100") (name "/PASTE_TDO") (class "Default")
      (node (ref "PASTE") (pin "71") (pinfunction "TDO/IO112_71") (pintype "bidirectional"))
    )
    (net (code "101") (name "/PASTE_TMS") (class "Default")
      (node (ref "PASTE") (pin "23") (pinfunction "IO48/TMS_23") (pintype "bidirectional"))
    )
    (net (code "102") (name "/PDS_+5V") (class "Default")
      (node (ref "JP1") (pin "1") (pinfunction "1_1") (pintype "passive"))
      (node (ref "JP2") (pin "1") (pinfunction "1_1") (pintype "passive"))
      (node (ref "JP3") (pin "1") (pinfunction "1_1") (pintype "passive"))
      (node (ref "X1") (pin "B13") (pinfunction "S_B13") (pintype "passive"))
      (node (ref "X1") (pin "B14") (pinfunction "S_B14") (pintype "passive"))
      (node (ref "X1") (pin "B15") (pinfunction "S_B15") (pintype "passive"))
      (node (ref "X1") (pin "B16") (pinfunction "S_B16") (pintype "passive"))
      (node (ref "X1") (pin "B17") (pinfunction "S_B17") (pintype "passive"))
      (node (ref "X1") (pin "C13") (pinfunction "S_C13") (pintype "passive"))
    )
    (net (code "103") (name "/PDS_A1") (class "Default")
      (node (ref "BUFALO") (pin "3") (pinfunction "A2_3") (pintype "bidirectional"))
      (node (ref "X1") (pin "A4") (pinfunction "S_A4") (pintype "passive"))
    )
    (net (code "104") (name "/PDS_A2") (class "Default")
      (node (ref "BUFALO") (pin "4") (pinfunction "A3_4") (pintype "bidirectional"))
      (node (ref "X1") (pin "A5") (pinfunction "S_A5") (pintype "passive"))
    )
    (net (code "105") (name "/PDS_A3") (class "Default")
      (node (ref "BUFALO") (pin "5") (pinfunction "A4_5") (pintype "bidirectional"))
      (node (ref "X1") (pin "A6") (pinfunction "S_A6") (pintype "passive"))
    )
    (net (code "106") (name "/PDS_A4") (class "Default")
      (node (ref "BUFALO") (pin "6") (pinfunction "A5_6") (pintype "bidirectional"))
      (node (ref "X1") (pin "A7") (pinfunction "S_A7") (pintype "passive"))
    )
    (net (code "107") (name "/PDS_A5") (class "Default")
      (node (ref "BUFALO") (pin "7") (pinfunction "A6_7") (pintype "bidirectional"))
      (node (ref "X1") (pin "A8") (pinfunction "S_A8") (pintype "passive"))
    )
    (net (code "108") (name "/PDS_A6") (class "Default")
      (node (ref "BUFALO") (pin "8") (pinfunction "A7_8") (pintype "bidirectional"))
      (node (ref "X1") (pin "A9") (pinfunction "S_A9") (pintype "passive"))
    )
    (net (code "109") (name "/PDS_A7") (class "Default")
      (node (ref "BUFALO") (pin "9") (pinfunction "A8_9") (pintype "bidirectional"))
      (node (ref "X1") (pin "A10") (pinfunction "S_A10") (pintype "passive"))
    )
    (net (code "110") (name "/PDS_A8") (class "Default")
      (node (ref "BUFAMID") (pin "2") (pinfunction "A1_2") (pintype "bidirectional"))
      (node (ref "X1") (pin "A11") (pinfunction "S_A11") (pintype "passive"))
    )
    (net (code "111") (name "/PDS_A9") (class "Default")
      (node (ref "BUFAMID") (pin "3") (pinfunction "A2_3") (pintype "bidirectional"))
      (node (ref "X1") (pin "A12") (pinfunction "S_A12") (pintype "passive"))
    )
    (net (code "112") (name "/PDS_A10") (class "Default")
      (node (ref "BUFAMID") (pin "4") (pinfunction "A3_4") (pintype "bidirectional"))
      (node (ref "X1") (pin "A13") (pinfunction "S_A13") (pintype "passive"))
    )
    (net (code "113") (name "/PDS_A11") (class "Default")
      (node (ref "BUFAMID") (pin "5") (pinfunction "A4_5") (pintype "bidirectional"))
      (node (ref "X1") (pin "A14") (pinfunction "S_A14") (pintype "passive"))
    )
    (net (code "114") (name "/PDS_A12") (class "Default")
      (node (ref "BUFAMID") (pin "6") (pinfunction "A5_6") (pintype "bidirectional"))
      (node (ref "X1") (pin "A15") (pinfunction "S_A15") (pintype "passive"))
    )
    (net (code "115") (name "/PDS_A13") (class "Default")
      (node (ref "BUFAMID") (pin "7") (pinfunction "A6_7") (pintype "bidirectional"))
      (node (ref "X1") (pin "A16") (pinfunction "S_A16") (pintype "passive"))
    )
    (net (code "116") (name "/PDS_A14") (class "Default")
      (node (ref "BUFAMID") (pin "8") (pinfunction "A7_8") (pintype "bidirectional"))
      (node (ref "X1") (pin "A17") (pinfunction "S_A17") (pintype "passive"))
    )
    (net (code "117") (name "/PDS_A15") (class "Default")
      (node (ref "BUFAMID") (pin "9") (pinfunction "A8_9") (pintype "bidirectional"))
      (node (ref "X1") (pin "A18") (pinfunction "S_A18") (pintype "passive"))
    )
    (net (code "118") (name "/PDS_A16") (class "Default")
      (node (ref "BUFAHI") (pin "2") (pinfunction "A1_2") (pintype "bidirectional"))
      (node (ref "X1") (pin "A19") (pinfunction "S_A19") (pintype "passive"))
    )
    (net (code "119") (name "/PDS_A17") (class "Default")
      (node (ref "BUFAHI") (pin "3") (pinfunction "A2_3") (pintype "bidirectional"))
      (node (ref "X1") (pin "A20") (pinfunction "S_A20") (pintype "passive"))
    )
    (net (code "120") (name "/PDS_A18") (class "Default")
      (node (ref "BUFAHI") (pin "4") (pinfunction "A3_4") (pintype "bidirectional"))
      (node (ref "X1") (pin "A21") (pinfunction "S_A21") (pintype "passive"))
    )
    (net (code "121") (name "/PDS_A19") (class "Default")
      (node (ref "BUFAHI") (pin "5") (pinfunction "A4_5") (pintype "bidirectional"))
      (node (ref "X1") (pin "A22") (pinfunction "S_A22") (pintype "passive"))
    )
    (net (code "122") (name "/PDS_A20") (class "Default")
      (node (ref "BUFAHI") (pin "6") (pinfunction "A5_6") (pintype "bidirectional"))
      (node (ref "X1") (pin "A23") (pinfunction "S_A23") (pintype "passive"))
    )
    (net (code "123") (name "/PDS_A21") (class "Default")
      (node (ref "BUFAHI") (pin "7") (pinfunction "A6_7") (pintype "bidirectional"))
      (node (ref "X1") (pin "A24") (pinfunction "S_A24") (pintype "passive"))
    )
    (net (code "124") (name "/PDS_A22") (class "Default")
      (node (ref "BUFAHI") (pin "8") (pinfunction "A7_8") (pintype "bidirectional"))
      (node (ref "X1") (pin "A25") (pinfunction "S_A25") (pintype "passive"))
    )
    (net (code "125") (name "/PDS_A23") (class "Default")
      (node (ref "BUFAHI") (pin "9") (pinfunction "A8_9") (pintype "bidirectional"))
      (node (ref "X1") (pin "A26") (pinfunction "S_A26") (pintype "passive"))
    )
    (net (code "126") (name "/PDS_C8M") (class "Default")
      (node (ref "PASTE") (pin "2") (pinfunction "OE2-GCLK2_2") (pintype "input"))
      (node (ref "X1") (pin "A28") (pinfunction "S_A28") (pintype "passive"))
    )
    (net (code "127") (name "/PDS_C16M") (class "Default")
      (node (ref "X1") (pin "A29") (pinfunction "S_A29") (pintype "passive"))
    )
    (net (code "128") (name "/PDS_D0") (class "Default")
      (node (ref "BUFDLO1") (pin "2") (pinfunction "A1_2") (pintype "bidirectional"))
      (node (ref "BUFDLO2") (pin "2") (pinfunction "A1_2") (pintype "bidirectional"))
      (node (ref "X1") (pin "C14") (pinfunction "S_C14") (pintype "passive"))
    )
    (net (code "129") (name "/PDS_D1") (class "Default")
      (node (ref "BUFDLO1") (pin "3") (pinfunction "A2_3") (pintype "bidirectional"))
      (node (ref "BUFDLO2") (pin "3") (pinfunction "A2_3") (pintype "bidirectional"))
      (node (ref "X1") (pin "C15") (pinfunction "S_C15") (pintype "passive"))
    )
    (net (code "130") (name "/PDS_D2") (class "Default")
      (node (ref "BUFDLO1") (pin "4") (pinfunction "A3_4") (pintype "bidirectional"))
      (node (ref "BUFDLO2") (pin "4") (pinfunction "A3_4") (pintype "bidirectional"))
      (node (ref "X1") (pin "C16") (pinfunction "S_C16") (pintype "passive"))
    )
    (net (code "131") (name "/PDS_D3") (class "Default")
      (node (ref "BUFDLO1") (pin "5") (pinfunction "A4_5") (pintype "bidirectional"))
      (node (ref "BUFDLO2") (pin "5") (pinfunction "A4_5") (pintype "bidirectional"))
      (node (ref "X1") (pin "C17") (pinfunction "S_C17") (pintype "passive"))
    )
    (net (code "132") (name "/PDS_D4") (class "Default")
      (node (ref "BUFDLO1") (pin "6") (pinfunction "A5_6") (pintype "bidirectional"))
      (node (ref "BUFDLO2") (pin "6") (pinfunction "A5_6") (pintype "bidirectional"))
      (node (ref "X1") (pin "C18") (pinfunction "S_C18") (pintype "passive"))
    )
    (net (code "133") (name "/PDS_D5") (class "Default")
      (node (ref "BUFDLO1") (pin "7") (pinfunction "A6_7") (pintype "bidirectional"))
      (node (ref "BUFDLO2") (pin "7") (pinfunction "A6_7") (pintype "bidirectional"))
      (node (ref "X1") (pin "C19") (pinfunction "S_C19") (pintype "passive"))
    )
    (net (code "134") (name "/PDS_D6") (class "Default")
      (node (ref "BUFDLO1") (pin "8") (pinfunction "A7_8") (pintype "bidirectional"))
      (node (ref "BUFDLO2") (pin "8") (pinfunction "A7_8") (pintype "bidirectional"))
      (node (ref "X1") (pin "C20") (pinfunction "S_C20") (pintype "passive"))
    )
    (net (code "135") (name "/PDS_D7") (class "Default")
      (node (ref "BUFDLO1") (pin "9") (pinfunction "A8_9") (pintype "bidirectional"))
      (node (ref "BUFDLO2") (pin "9") (pinfunction "A8_9") (pintype "bidirectional"))
      (node (ref "X1") (pin "C21") (pinfunction "S_C21") (pintype "passive"))
    )
    (net (code "136") (name "/PDS_D8") (class "Default")
      (node (ref "BUFDHI") (pin "2") (pinfunction "A1_2") (pintype "bidirectional"))
      (node (ref "X1") (pin "C22") (pinfunction "S_C22") (pintype "passive"))
    )
    (net (code "137") (name "/PDS_D9") (class "Default")
      (node (ref "BUFDHI") (pin "3") (pinfunction "A2_3") (pintype "bidirectional"))
      (node (ref "X1") (pin "C23") (pinfunction "S_C23") (pintype "passive"))
    )
    (net (code "138") (name "/PDS_D10") (class "Default")
      (node (ref "BUFDHI") (pin "4") (pinfunction "A3_4") (pintype "bidirectional"))
      (node (ref "X1") (pin "C24") (pinfunction "S_C24") (pintype "passive"))
    )
    (net (code "139") (name "/PDS_D11") (class "Default")
      (node (ref "BUFDHI") (pin "5") (pinfunction "A4_5") (pintype "bidirectional"))
      (node (ref "X1") (pin "C25") (pinfunction "S_C25") (pintype "passive"))
    )
    (net (code "140") (name "/PDS_D12") (class "Default")
      (node (ref "BUFDHI") (pin "6") (pinfunction "A5_6") (pintype "bidirectional"))
      (node (ref "X1") (pin "C26") (pinfunction "S_C26") (pintype "passive"))
    )
    (net (code "141") (name "/PDS_D13") (class "Default")
      (node (ref "BUFDHI") (pin "7") (pinfunction "A6_7") (pintype "bidirectional"))
      (node (ref "X1") (pin "C27") (pinfunction "S_C27") (pintype "passive"))
    )
    (net (code "142") (name "/PDS_D14") (class "Default")
      (node (ref "BUFDHI") (pin "8") (pinfunction "A7_8") (pintype "bidirectional"))
      (node (ref "X1") (pin "C28") (pinfunction "S_C28") (pintype "passive"))
    )
    (net (code "143") (name "/PDS_D15") (class "Default")
      (node (ref "BUFDHI") (pin "9") (pinfunction "A8_9") (pintype "bidirectional"))
      (node (ref "X1") (pin "C29") (pinfunction "S_C29") (pintype "passive"))
    )
    (net (code "144") (name "/PDS_E-CLK") (class "Default")
      (node (ref "PASTE") (pin "49") (pinfunction "IO73_49") (pintype "bidirectional"))
      (node (ref "X1") (pin "A27") (pinfunction "S_A27") (pintype "passive"))
    )
    (net (code "145") (name "/PDS_FC0") (class "Default")
      (node (ref "BUFC") (pin "11") (pinfunction "B8_11") (pintype "bidirectional"))
      (node (ref "X1") (pin "A3") (pinfunction "S_A3") (pintype "passive"))
    )
    (net (code "146") (name "/PDS_FC1") (class "Default")
      (node (ref "BUFC") (pin "12") (pinfunction "B7_12") (pintype "bidirectional"))
      (node (ref "X1") (pin "A2") (pinfunction "S_A2") (pintype "passive"))
    )
    (net (code "147") (name "/PDS_FC2") (class "Default")
      (node (ref "BUFC") (pin "13") (pinfunction "B6_13") (pintype "bidirectional"))
      (node (ref "X1") (pin "A1") (pinfunction "S_A1") (pintype "passive"))
    )
    (net (code "148") (name "/PDS_R{slash}~{W}") (class "Default")
      (node (ref "BUFC") (pin "14") (pinfunction "B5_14") (pintype "bidirectional"))
      (node (ref "X1") (pin "C7") (pinfunction "S_C7") (pintype "passive"))
    )
    (net (code "149") (name "/PDS_~{AS}") (class "Default")
      (node (ref "BUFC") (pin "15") (pinfunction "B4_15") (pintype "bidirectional"))
      (node (ref "X1") (pin "C10") (pinfunction "S_C10") (pintype "passive"))
    )
    (net (code "150") (name "/PDS_~{BERR}") (class "Default")
      (node (ref "X1") (pin "B21") (pinfunction "S_B21") (pintype "passive"))
    )
    (net (code "151") (name "/PDS_~{BGACK}") (class "Default")
      (node (ref "PASTE") (pin "58") (pinfunction "IO91_58") (pintype "bidirectional"))
      (node (ref "X1") (pin "C4") (pinfunction "S_C4") (pintype "passive"))
    )
    (net (code "152") (name "/PDS_~{BG}") (class "Default")
      (node (ref "PASTE") (pin "61") (pinfunction "IO94_61") (pintype "bidirectional"))
      (node (ref "X1") (pin "C5") (pinfunction "S_C5") (pintype "passive"))
    )
    (net (code "153") (name "/PDS_~{BR}") (class "Default")
      (node (ref "PASTE") (pin "56") (pinfunction "IO86_56") (pintype "bidirectional"))
      (node (ref "X1") (pin "C3") (pinfunction "S_C3") (pintype "passive"))
    )
    (net (code "154") (name "/PDS_~{DTACK}") (class "Default")
      (node (ref "PASTE") (pin "65") (pinfunction "IO101_65") (pintype "bidirectional"))
      (node (ref "X1") (pin "C6") (pinfunction "S_C6") (pintype "passive"))
    )
    (net (code "155") (name "/PDS_~{EXT-DTK}") (class "Default")
      (node (ref "X1") (pin "B28") (pinfunction "S_B28") (pintype "passive"))
    )
    (net (code "156") (name "/PDS_~{HALT}") (class "Default")
      (node (ref "X1") (pin "B12") (pinfunction "S_B12") (pintype "passive"))
    )
    (net (code "157") (name "/PDS_~{IPL0}") (class "Default")
      (node (ref "X1") (pin "B18") (pinfunction "S_B18") (pintype "passive"))
    )
    (net (code "158") (name "/PDS_~{IPL1}") (class "Default")
      (node (ref "X1") (pin "B19") (pinfunction "S_B19") (pintype "passive"))
    )
    (net (code "159") (name "/PDS_~{IPL2}") (class "Default")
      (node (ref "X1") (pin "B20") (pinfunction "S_B20") (pintype "passive"))
    )
    (net (code "160") (name "/PDS_~{LDS}") (class "Default")
      (node (ref "PASTE") (pin "63") (pinfunction "IO97_63") (pintype "bidirectional"))
      (node (ref "X1") (pin "C8") (pinfunction "S_C8") (pintype "passive"))
    )
    (net (code "161") (name "/PDS_~{PMCYC}") (class "Default")
      (node (ref "X1") (pin "C11") (pinfunction "S_C11") (pintype "passive"))
    )
    (net (code "162") (name "/PDS_~{RESET}") (class "Default")
      (node (ref "PASTE") (pin "1") (pinfunction "GCLR/_1") (pintype "input"))
      (node (ref "X1") (pin "C12") (pinfunction "S_C12") (pintype "passive"))
    )
    (net (code "163") (name "/PDS_~{UDS}") (class "Default")
      (node (ref "PASTE") (pin "60") (pinfunction "IO93_60") (pintype "bidirectional"))
      (node (ref "X1") (pin "C9") (pinfunction "S_C9") (pintype "passive"))
    )
    (net (code "164") (name "/PDS_~{VMA}") (class "Default")
      (node (ref "PASTE") (pin "48") (pinfunction "IO72_48") (pintype "bidirectional"))
      (node (ref "X1") (pin "C2") (pinfunction "S_C2") (pintype "passive"))
    )
    (net (code "165") (name "/PDS_~{VPA}") (class "Default")
      (node (ref "PASTE") (pin "50") (pinfunction "IO75_50") (pintype "bidirectional"))
      (node (ref "X1") (pin "C1") (pinfunction "S_C1") (pintype "passive"))
    )
    (net (code "166") (name "/~{BUFAEN}") (class "Default")
      (node (ref "BUFAHI") (pin "19") (pinfunction "G_19") (pintype "input"))
      (node (ref "BUFALO") (pin "19") (pinfunction "G_19") (pintype "input"))
      (node (ref "BUFAMID") (pin "19") (pinfunction "G_19") (pintype "input"))
      (node (ref "PASTE") (pin "37") (pinfunction "IO56_37") (pintype "bidirectional"))
    )
    (net (code "167") (name "/~{BUFCEN}") (class "Default")
      (node (ref "BUFC") (pin "19") (pinfunction "G_19") (pintype "input"))
      (node (ref "PASTE") (pin "81") (pinfunction "IO128_81") (pintype "bidirectional"))
    )
    (net (code "168") (name "/~{BUFDHIEN}") (class "Default")
      (node (ref "BUFDHI") (pin "19") (pinfunction "G_19") (pintype "input"))
      (node (ref "PASTE") (pin "46") (pinfunction "IO69_46") (pintype "bidirectional"))
    )
    (net (code "169") (name "/~{BUFDLO1EN}") (class "Default")
      (node (ref "BUFDLO1") (pin "19") (pinfunction "G_19") (pintype "input"))
      (node (ref "PASTE") (pin "39") (pinfunction "IO53_39") (pintype "bidirectional"))
    )
    (net (code "170") (name "/~{BUFDLO2EN}") (class "Default")
      (node (ref "BUFDLO2") (pin "19") (pinfunction "G_19") (pintype "input"))
      (node (ref "PASTE") (pin "40") (pinfunction "IO51_40") (pintype "bidirectional"))
    )
    (net (code "171") (name "SUPPLY1_VCC") (class "Default")
      (node (ref "BUFC") (pin "1") (pinfunction "DIR_1") (pintype "input"))
      (node (ref "C1") (pin "1") (pinfunction "1_1") (pintype "passive"))
      (node (ref "C10") (pin "1") (pinfunction "1_1") (pintype "passive"))
      (node (ref "C11") (pin "1") (pinfunction "1_1") (pintype "passive"))
      (node (ref "C12") (pin "1") (pinfunction "1_1") (pintype "passive"))
      (node (ref "C13") (pin "1") (pinfunction "1_1") (pintype "passive"))
      (node (ref "C14") (pin "1") (pinfunction "1_1") (pintype "passive"))
      (node (ref "C15") (pin "1") (pinfunction "1_1") (pintype "passive"))
      (node (ref "C16") (pin "1") (pinfunction "1_1") (pintype "passive"))
      (node (ref "C17") (pin "1") (pinfunction "1_1") (pintype "passive"))
      (node (ref "C18") (pin "1") (pinfunction "1_1") (pintype "passive"))
      (node (ref "C19") (pin "1") (pinfunction "1_1") (pintype "passive"))
      (node (ref "C2") (pin "1") (pinfunction "1_1") (pintype "passive"))
      (node (ref "C20") (pin "1") (pinfunction "1_1") (pintype "passive"))
      (node (ref "C21") (pin "1") (pinfunction "1_1") (pintype "passive"))
      (node (ref "C22") (pin "1") (pinfunction "1_1") (pintype "passive"))
      (node (ref "C23") (pin "1") (pinfunction "1_1") (pintype "passive"))
      (node (ref "C24") (pin "1") (pinfunction "1_1") (pintype "passive"))
      (node (ref "C25") (pin "1") (pinfunction "1_1") (pintype "passive"))
      (node (ref "C26") (pin "1") (pinfunction "1_1") (pintype "passive"))
      (node (ref "C27") (pin "+") (pinfunction "+_+") (pintype "passive"))
      (node (ref "C28") (pin "+") (pinfunction "+_+") (pintype "passive"))
      (node (ref "C29") (pin "1") (pinfunction "1_1") (pintype "passive"))
      (node (ref "C3") (pin "1") (pinfunction "1_1") (pintype "passive"))
      (node (ref "C30") (pin "1") (pinfunction "1_1") (pintype "passive"))
      (node (ref "C31") (pin "1") (pinfunction "1_1") (pintype "passive"))
      (node (ref "C32") (pin "1") (pinfunction "1_1") (pintype "passive"))
      (node (ref "C33") (pin "1") (pinfunction "1_1") (pintype "passive"))
      (node (ref "C34") (pin "1") (pinfunction "1_1") (pintype "passive"))
      (node (ref "C35") (pin "1") (pinfunction "1_1") (pintype "passive"))
      (node (ref "C4") (pin "1") (pinfunction "1_1") (pintype "passive"))
      (node (ref "C5") (pin "1") (pinfunction "1_1") (pintype "passive"))
      (node (ref "C6") (pin "1") (pinfunction "1_1") (pintype "passive"))
      (node (ref "C7") (pin "1") (pinfunction "1_1") (pintype "passive"))
      (node (ref "C8") (pin "1") (pinfunction "1_1") (pintype "passive"))
      (node (ref "C9") (pin "1") (pinfunction "1_1") (pintype "passive"))
      (node (ref "CLOCK") (pin "8") (pinfunction "VCC_8") (pintype "power_in"))
      (node (ref "CPU") (pin "C06") (pinfunction "VCC_C06") (pintype "power_in"))
      (node (ref "CPU") (pin "D04") (pinfunction "VCC_D04") (pintype "power_in"))
      (node (ref "CPU") (pin "D10") (pinfunction "VCC_D10") (pintype "power_in"))
      (node (ref "CPU") (pin "F02") (pinfunction "VCC_F02") (pintype "power_in"))
      (node (ref "CPU") (pin "F11") (pinfunction "VCC_F11") (pintype "power_in"))
      (node (ref "CPU") (pin "H03") (pinfunction "VCC_H03") (pintype "power_in"))
      (node (ref "CPU") (pin "H11") (pinfunction "VCC_H11") (pintype "power_in"))
      (node (ref "CPU") (pin "K04") (pinfunction "VCC_K04") (pintype "power_in"))
      (node (ref "CPU") (pin "K10") (pinfunction "VCC_K10") (pintype "power_in"))
      (node (ref "CPU") (pin "L06") (pinfunction "VCC_L06") (pintype "power_in"))
      (node (ref "FPU") (pin "A01") (pinfunction "VCC_A01") (pintype "power_in"))
      (node (ref "FPU") (pin "B01") (pinfunction "VCC_B01") (pintype "power_in"))
      (node (ref "FPU") (pin "B08") (pinfunction "VCC_B08") (pintype "power_in"))
      (node (ref "FPU") (pin "E02") (pinfunction "VCC_E02") (pintype "power_in"))
      (node (ref "FPU") (pin "E09") (pinfunction "VCC_E09") (pintype "power_in"))
      (node (ref "FPU") (pin "F01") (pinfunction "SIZE_F01") (pintype "input"))
      (node (ref "FPU") (pin "H03") (pinfunction "A0_H03") (pintype "input"))
      (node (ref "FPU") (pin "H08") (pinfunction "VCC_H08") (pintype "power_in"))
      (node (ref "FPU") (pin "J02") (pinfunction "VCC_J02") (pintype "power_in"))
      (node (ref "JP1") (pin "2") (pinfunction "2_2") (pintype "passive"))
      (node (ref "JP2") (pin "2") (pinfunction "2_2") (pintype "passive"))
      (node (ref "JP3") (pin "2") (pinfunction "2_2") (pintype "passive"))
      (node (ref "PASTE") (pin "13") (pinfunction "VCCIO_13") (pintype "power_in"))
      (node (ref "PASTE") (pin "26") (pinfunction "VCCIO_26") (pintype "power_in"))
      (node (ref "PASTE") (pin "3") (pinfunction "VCC_3") (pintype "power_in"))
      (node (ref "PASTE") (pin "38") (pinfunction "VCCIO_38") (pintype "power_in"))
      (node (ref "PASTE") (pin "43") (pinfunction "VCC_43") (pintype "power_in"))
      (node (ref "PASTE") (pin "53") (pinfunction "VCCIO_53") (pintype "power_in"))
      (node (ref "PASTE") (pin "66") (pinfunction "VCCIO_66") (pintype "power_in"))
      (node (ref "PASTE") (pin "78") (pinfunction "VCCIO_78") (pintype "power_in"))
      (node (ref "POWER") (pin "4") (pinfunction "S_4") (pintype "passive"))
      (node (ref "R1") (pin "2") (pinfunction "2_2") (pintype "passive"))
      (node (ref "R10") (pin "2") (pinfunction "2_2") (pintype "passive"))
      (node (ref "R11") (pin "2") (pinfunction "2_2") (pintype "passive"))
      (node (ref "R12") (pin "2") (pinfunction "2_2") (pintype "passive"))
      (node (ref "R13") (pin "2") (pinfunction "2_2") (pintype "passive"))
      (node (ref "R14") (pin "2") (pinfunction "2_2") (pintype "passive"))
      (node (ref "R15") (pin "2") (pinfunction "2_2") (pintype "passive"))
      (node (ref "R16") (pin "2") (pinfunction "2_2") (pintype "passive"))
      (node (ref "R2") (pin "2") (pinfunction "2_2") (pintype "passive"))
      (node (ref "R3") (pin "2") (pinfunction "2_2") (pintype "passive"))
      (node (ref "R4") (pin "2") (pinfunction "2_2") (pintype "passive"))
      (node (ref "R5") (pin "2") (pinfunction "2_2") (pintype "passive"))
      (node (ref "R6") (pin "2") (pinfunction "2_2") (pintype "passive"))
      (node (ref "R7") (pin "2") (pinfunction "2_2") (pintype "passive"))
      (node (ref "R8") (pin "2") (pinfunction "2_2") (pintype "passive"))
      (node (ref "R9") (pin "2") (pinfunction "2_2") (pintype "passive"))
    )
    (net (code "172") (name "SUPPLY2_GND") (class "Default")
      (node (ref "BUFAHI") (pin "1") (pinfunction "DIR_1") (pintype "input"))
      (node (ref "BUFALO") (pin "1") (pinfunction "DIR_1") (pintype "input"))
      (node (ref "BUFALO") (pin "18") (pinfunction "B1_18") (pintype "bidirectional"))
      (node (ref "BUFALO") (pin "2") (pinfunction "A1_2") (pintype "bidirectional"))
      (node (ref "BUFAMID") (pin "1") (pinfunction "DIR_1") (pintype "input"))
      (node (ref "BUFC") (pin "16") (pinfunction "B3_16") (pintype "bidirectional"))
      (node (ref "BUFC") (pin "17") (pinfunction "B2_17") (pintype "bidirectional"))
      (node (ref "BUFC") (pin "18") (pinfunction "B1_18") (pintype "bidirectional"))
      (node (ref "BUFC") (pin "2") (pinfunction "A1_2") (pintype "bidirectional"))
      (node (ref "BUFC") (pin "3") (pinfunction "A2_3") (pintype "bidirectional"))
      (node (ref "BUFC") (pin "4") (pinfunction "A3_4") (pintype "bidirectional"))
      (node (ref "C1") (pin "2") (pinfunction "2_2") (pintype "passive"))
      (node (ref "C10") (pin "2") (pinfunction "2_2") (pintype "passive"))
      (node (ref "C11") (pin "2") (pinfunction "2_2") (pintype "passive"))
      (node (ref "C12") (pin "2") (pinfunction "2_2") (pintype "passive"))
      (node (ref "C13") (pin "2") (pinfunction "2_2") (pintype "passive"))
      (node (ref "C14") (pin "2") (pinfunction "2_2") (pintype "passive"))
      (node (ref "C15") (pin "2") (pinfunction "2_2") (pintype "passive"))
      (node (ref "C16") (pin "2") (pinfunction "2_2") (pintype "passive"))
      (node (ref "C17") (pin "2") (pinfunction "2_2") (pintype "passive"))
      (node (ref "C18") (pin "2") (pinfunction "2_2") (pintype "passive"))
      (node (ref "C19") (pin "2") (pinfunction "2_2") (pintype "passive"))
      (node (ref "C2") (pin "2") (pinfunction "2_2") (pintype "passive"))
      (node (ref "C20") (pin "2") (pinfunction "2_2") (pintype "passive"))
      (node (ref "C21") (pin "2") (pinfunction "2_2") (pintype "passive"))
      (node (ref "C22") (pin "2") (pinfunction "2_2") (pintype "passive"))
      (node (ref "C23") (pin "2") (pinfunction "2_2") (pintype "passive"))
      (node (ref "C24") (pin "2") (pinfunction "2_2") (pintype "passive"))
      (node (ref "C25") (pin "2") (pinfunction "2_2") (pintype "passive"))
      (node (ref "C26") (pin "2") (pinfunction "2_2") (pintype "passive"))
      (node (ref "C27") (pin "-") (pinfunction "-_-") (pintype "passive"))
      (node (ref "C28") (pin "-") (pinfunction "-_-") (pintype "passive"))
      (node (ref "C29") (pin "2") (pinfunction "2_2") (pintype "passive"))
      (node (ref "C3") (pin "2") (pinfunction "2_2") (pintype "passive"))
      (node (ref "C30") (pin "2") (pinfunction "2_2") (pintype "passive"))
      (node (ref "C31") (pin "2") (pinfunction "2_2") (pintype "passive"))
      (node (ref "C32") (pin "2") (pinfunction "2_2") (pintype "passive"))
      (node (ref "C33") (pin "2") (pinfunction "2_2") (pintype "passive"))
      (node (ref "C34") (pin "2") (pinfunction "2_2") (pintype "passive"))
      (node (ref "C35") (pin "2") (pinfunction "2_2") (pintype "passive"))
      (node (ref "C4") (pin "2") (pinfunction "2_2") (pintype "passive"))
      (node (ref "C5") (pin "2") (pinfunction "2_2") (pintype "passive"))
      (node (ref "C6") (pin "2") (pinfunction "2_2") (pintype "passive"))
      (node (ref "C7") (pin "2") (pinfunction "2_2") (pintype "passive"))
      (node (ref "C8") (pin "2") (pinfunction "2_2") (pintype "passive"))
      (node (ref "C9") (pin "2") (pinfunction "2_2") (pintype "passive"))
      (node (ref "CLOCK") (pin "4") (pinfunction "GND_4") (pintype "power_in"))
      (node (ref "CPU") (pin "C05") (pinfunction "GND_C05") (pintype "power_in"))
      (node (ref "CPU") (pin "C07") (pinfunction "GND_C07") (pintype "power_in"))
      (node (ref "CPU") (pin "C09") (pinfunction "GND_C09") (pintype "power_in"))
      (node (ref "CPU") (pin "E03") (pinfunction "GND_E03") (pintype "power_in"))
      (node (ref "CPU") (pin "E11") (pinfunction "GND_E11") (pintype "power_in"))
      (node (ref "CPU") (pin "F03") (pinfunction "GND_F03") (pintype "power_in"))
      (node (ref "CPU") (pin "G03") (pinfunction "GND_G03") (pintype "power_in"))
      (node (ref "CPU") (pin "G11") (pinfunction "GND_G11") (pintype "power_in"))
      (node (ref "CPU") (pin "J03") (pinfunction "GND_J03") (pintype "power_in"))
      (node (ref "CPU") (pin "J11") (pinfunction "GND_J11") (pintype "power_in"))
      (node (ref "CPU") (pin "L05") (pinfunction "GND_L05") (pintype "power_in"))
      (node (ref "CPU") (pin "L07") (pinfunction "GND_L07") (pintype "power_in"))
      (node (ref "CPU") (pin "L08") (pinfunction "GND_L08") (pintype "power_in"))
      (node (ref "CPU") (pin "L09") (pinfunction "GND_L09") (pintype "power_in"))
      (node (ref "FPU") (pin "A02") (pinfunction "GND_A02") (pintype "power_in"))
      (node (ref "FPU") (pin "A10") (pinfunction "GND_A10") (pintype "power_in"))
      (node (ref "FPU") (pin "B02") (pinfunction "GND_B02") (pintype "power_in"))
      (node (ref "FPU") (pin "B03") (pinfunction "GND_B03") (pintype "power_in"))
      (node (ref "FPU") (pin "B07") (pinfunction "GND_B07") (pintype "power_in"))
      (node (ref "FPU") (pin "C01") (pinfunction "GND_C01") (pintype "power_in"))
      (node (ref "FPU") (pin "C03") (pinfunction "GND_C03") (pintype "power_in"))
      (node (ref "FPU") (pin "D02") (pinfunction "GND_D02") (pintype "power_in"))
      (node (ref "FPU") (pin "E10") (pinfunction "GND_E10") (pintype "power_in"))
      (node (ref "FPU") (pin "F02") (pinfunction "GND_F02") (pintype "power_in"))
      (node (ref "FPU") (pin "H09") (pinfunction "GND_H09") (pintype "power_in"))
      (node (ref "FPU") (pin "J08") (pinfunction "GND_J08") (pintype "power_in"))
      (node (ref "FPU") (pin "K03") (pinfunction "GND_K03") (pintype "power_in"))
      (node (ref "PASTE") (pin "19") (pinfunction "GND_19") (pintype "power_in"))
      (node (ref "PASTE") (pin "32") (pinfunction "GND_32") (pintype "power_in"))
      (node (ref "PASTE") (pin "42") (pinfunction "GND_42") (pintype "power_in"))
      (node (ref "PASTE") (pin "47") (pinfunction "GND_47") (pintype "power_in"))
      (node (ref "PASTE") (pin "59") (pinfunction "GND_59") (pintype "power_in"))
      (node (ref "PASTE") (pin "7") (pinfunction "GND_7") (pintype "power_in"))
      (node (ref "PASTE") (pin "72") (pinfunction "GND_72") (pintype "power_in"))
      (node (ref "PASTE") (pin "82") (pinfunction "GND_82") (pintype "power_in"))
      (node (ref "POWER") (pin "3") (pinfunction "S_3") (pintype "passive"))
      (node (ref "X1") (pin "A30") (pinfunction "S_A30") (pintype "passive"))
      (node (ref "X1") (pin "B1") (pinfunction "S_B1") (pintype "passive"))
      (node (ref "X1") (pin "B2") (pinfunction "S_B2") (pintype "passive"))
      (node (ref "X1") (pin "B29") (pinfunction "S_B29") (pintype "passive"))
      (node (ref "X1") (pin "B3") (pinfunction "S_B3") (pintype "passive"))
      (node (ref "X1") (pin "B4") (pinfunction "S_B4") (pintype "passive"))
      (node (ref "X1") (pin "B5") (pinfunction "S_B5") (pintype "passive"))
      (node (ref "X1") (pin "B6") (pinfunction "S_B6") (pintype "passive"))
      (node (ref "X1") (pin "B7") (pinfunction "S_B7") (pintype "passive"))
      (node (ref "X1") (pin "B8") (pinfunction "S_B8") (pintype "passive"))
      (node (ref "X1") (pin "B9") (pinfunction "S_B9") (pintype "passive"))
      (node (ref "X1") (pin "C30") (pinfunction "S_C30") (pintype "passive"))
    )
    (net (code "173") (name "unconnected-(CPUA-CBREQ-PadK01)") (class "Default")
      (node (ref "CPU") (pin "K01") (pinfunction "CBREQ_K01") (pintype "output"))
    )
    (net (code "174") (name "unconnected-(CPUA-CIOUT-PadC02)") (class "Default")
      (node (ref "CPU") (pin "C02") (pinfunction "CIOUT_C02") (pintype "output"))
    )
    (net (code "175") (name "unconnected-(CPUA-ECS-PadM02)") (class "Default")
      (node (ref "CPU") (pin "M02") (pinfunction "ECS_M02") (pintype "output"))
    )
    (net (code "176") (name "unconnected-(CPUA-IPEND-PadE13)") (class "Default")
      (node (ref "CPU") (pin "E13") (pinfunction "IPEND_E13") (pintype "output"))
    )
    (net (code "177") (name "unconnected-(CPUA-OCS-PadD03)") (class "Default")
      (node (ref "CPU") (pin "D03") (pinfunction "OCS_D03") (pintype "output"))
    )
    (net (code "178") (name "unconnected-(CPUA-REFILL-PadJ13)") (class "Default")
      (node (ref "CPU") (pin "J13") (pinfunction "REFILL_J13") (pintype "output"))
    )
    (net (code "179") (name "unconnected-(CPUA-RMC-PadB01)") (class "Default")
      (node (ref "CPU") (pin "B01") (pinfunction "RMC_B01") (pintype "output"))
    )
    (net (code "180") (name "unconnected-(CPUA-STATUS-PadJ12)") (class "Default")
      (node (ref "CPU") (pin "J12") (pinfunction "STATUS_J12") (pintype "output"))
    )
    (net (code "181") (name "unconnected-(PASTEQ-IO14-Pad5)") (class "Default")
      (node (ref "PASTE") (pin "5") (pinfunction "IO14_5") (pintype "bidirectional"))
    )
    (net (code "182") (name "unconnected-(PASTEQ-IO16-Pad4)") (class "Default")
      (node (ref "PASTE") (pin "4") (pinfunction "IO16_4") (pintype "bidirectional"))
    )
    (net (code "183") (name "unconnected-(PASTEQ-IO49-Pad41)") (class "Default")
      (node (ref "PASTE") (pin "41") (pinfunction "IO49_41") (pintype "bidirectional"))
    )
    (net (code "184") (name "unconnected-(PASTEQ-IO65-Pad44)") (class "Default")
      (node (ref "PASTE") (pin "44") (pinfunction "IO65_44") (pintype "bidirectional"))
    )
    (net (code "185") (name "unconnected-(PASTEQ-IO67-Pad45)") (class "Default")
      (node (ref "PASTE") (pin "45") (pinfunction "IO67_45") (pintype "bidirectional"))
    )
    (net (code "186") (name "unconnected-(PASTEQ-IO77-Pad51)") (class "Default")
      (node (ref "PASTE") (pin "51") (pinfunction "IO77_51") (pintype "bidirectional"))
    )
    (net (code "187") (name "unconnected-(PASTEQ-IO80-Pad52)") (class "Default")
      (node (ref "PASTE") (pin "52") (pinfunction "IO80_52") (pintype "bidirectional"))
    )
    (net (code "188") (name "unconnected-(PASTEQ-IO83-Pad54)") (class "Default")
      (node (ref "PASTE") (pin "54") (pinfunction "IO83_54") (pintype "bidirectional"))
    )
    (net (code "189") (name "unconnected-(PASTEQ-IO85-Pad55)") (class "Default")
      (node (ref "PASTE") (pin "55") (pinfunction "IO85_55") (pintype "bidirectional"))
    )
    (net (code "190") (name "unconnected-(PASTEQ-IO88-Pad57)") (class "Default")
      (node (ref "PASTE") (pin "57") (pinfunction "IO88_57") (pintype "bidirectional"))
    )
    (net (code "191") (name "unconnected-(PASTEQ-IO115-Pad73)") (class "Default")
      (node (ref "PASTE") (pin "73") (pinfunction "IO115_73") (pintype "bidirectional"))
    )
    (net (code "192") (name "unconnected-(PASTEQ-IO117-Pad74)") (class "Default")
      (node (ref "PASTE") (pin "74") (pinfunction "IO117_74") (pintype "bidirectional"))
    )
    (net (code "193") (name "unconnected-(PASTEQ-IO118-Pad75)") (class "Default")
      (node (ref "PASTE") (pin "75") (pinfunction "IO118_75") (pintype "bidirectional"))
    )
    (net (code "194") (name "unconnected-(PASTEQ-IO120-Pad76)") (class "Default")
      (node (ref "PASTE") (pin "76") (pinfunction "IO120_76") (pintype "bidirectional"))
    )
    (net (code "195") (name "unconnected-(PASTEQ-IO123-Pad77)") (class "Default")
      (node (ref "PASTE") (pin "77") (pinfunction "IO123_77") (pintype "bidirectional"))
    )
    (net (code "196") (name "unconnected-(PASTEQ-IO125-Pad79)") (class "Default")
      (node (ref "PASTE") (pin "79") (pinfunction "IO125_79") (pintype "bidirectional"))
    )
    (net (code "197") (name "unconnected-(PASTEQ-OE1-Pad84)") (class "Default")
      (node (ref "PASTE") (pin "84") (pinfunction "OE1_84") (pintype "input"))
    )
    (net (code "198") (name "unconnected-(POWERA-S-Pad1)") (class "Default")
      (node (ref "POWER") (pin "1") (pinfunction "S_1") (pintype "passive"))
    )
    (net (code "199") (name "unconnected-(POWERB-S-Pad2)") (class "Default")
      (node (ref "POWER") (pin "2") (pinfunction "S_2") (pintype "passive"))
    )
    (net (code "200") (name "unconnected-(X1AH-S-PadB10)") (class "Default")
      (node (ref "X1") (pin "B10") (pinfunction "S_B10") (pintype "passive"))
    )
    (net (code "201") (name "unconnected-(X1AI-S-PadB11)") (class "Default")
      (node (ref "X1") (pin "B11") (pinfunction "S_B11") (pintype "passive"))
    )
    (net (code "202") (name "unconnected-(X1AU-S-PadB22)") (class "Default")
      (node (ref "X1") (pin "B22") (pinfunction "S_B22") (pintype "passive"))
    )
    (net (code "203") (name "unconnected-(X1AV-S-PadB23)") (class "Default")
      (node (ref "X1") (pin "B23") (pinfunction "S_B23") (pintype "passive"))
    )
    (net (code "204") (name "unconnected-(X1AW-S-PadB24)") (class "Default")
      (node (ref "X1") (pin "B24") (pinfunction "S_B24") (pintype "passive"))
    )
    (net (code "205") (name "unconnected-(X1AX-S-PadB25)") (class "Default")
      (node (ref "X1") (pin "B25") (pinfunction "S_B25") (pintype "passive"))
    )
    (net (code "206") (name "unconnected-(X1AY-S-PadB26)") (class "Default")
      (node (ref "X1") (pin "B26") (pinfunction "S_B26") (pintype "passive"))
    )
    (net (code "207") (name "unconnected-(X1AZ-S-PadB27)") (class "Default")
      (node (ref "X1") (pin "B27") (pinfunction "S_B27") (pintype "passive"))
    )
    (net (code "208") (name "unconnected-(X1CK-S-PadC31)") (class "Default")
      (node (ref "X1") (pin "C31") (pinfunction "S_C31") (pintype "passive"))
    )
  )
)
